# untitled2-6.net
KiCad netlist of a schematic drawn in EAGLE
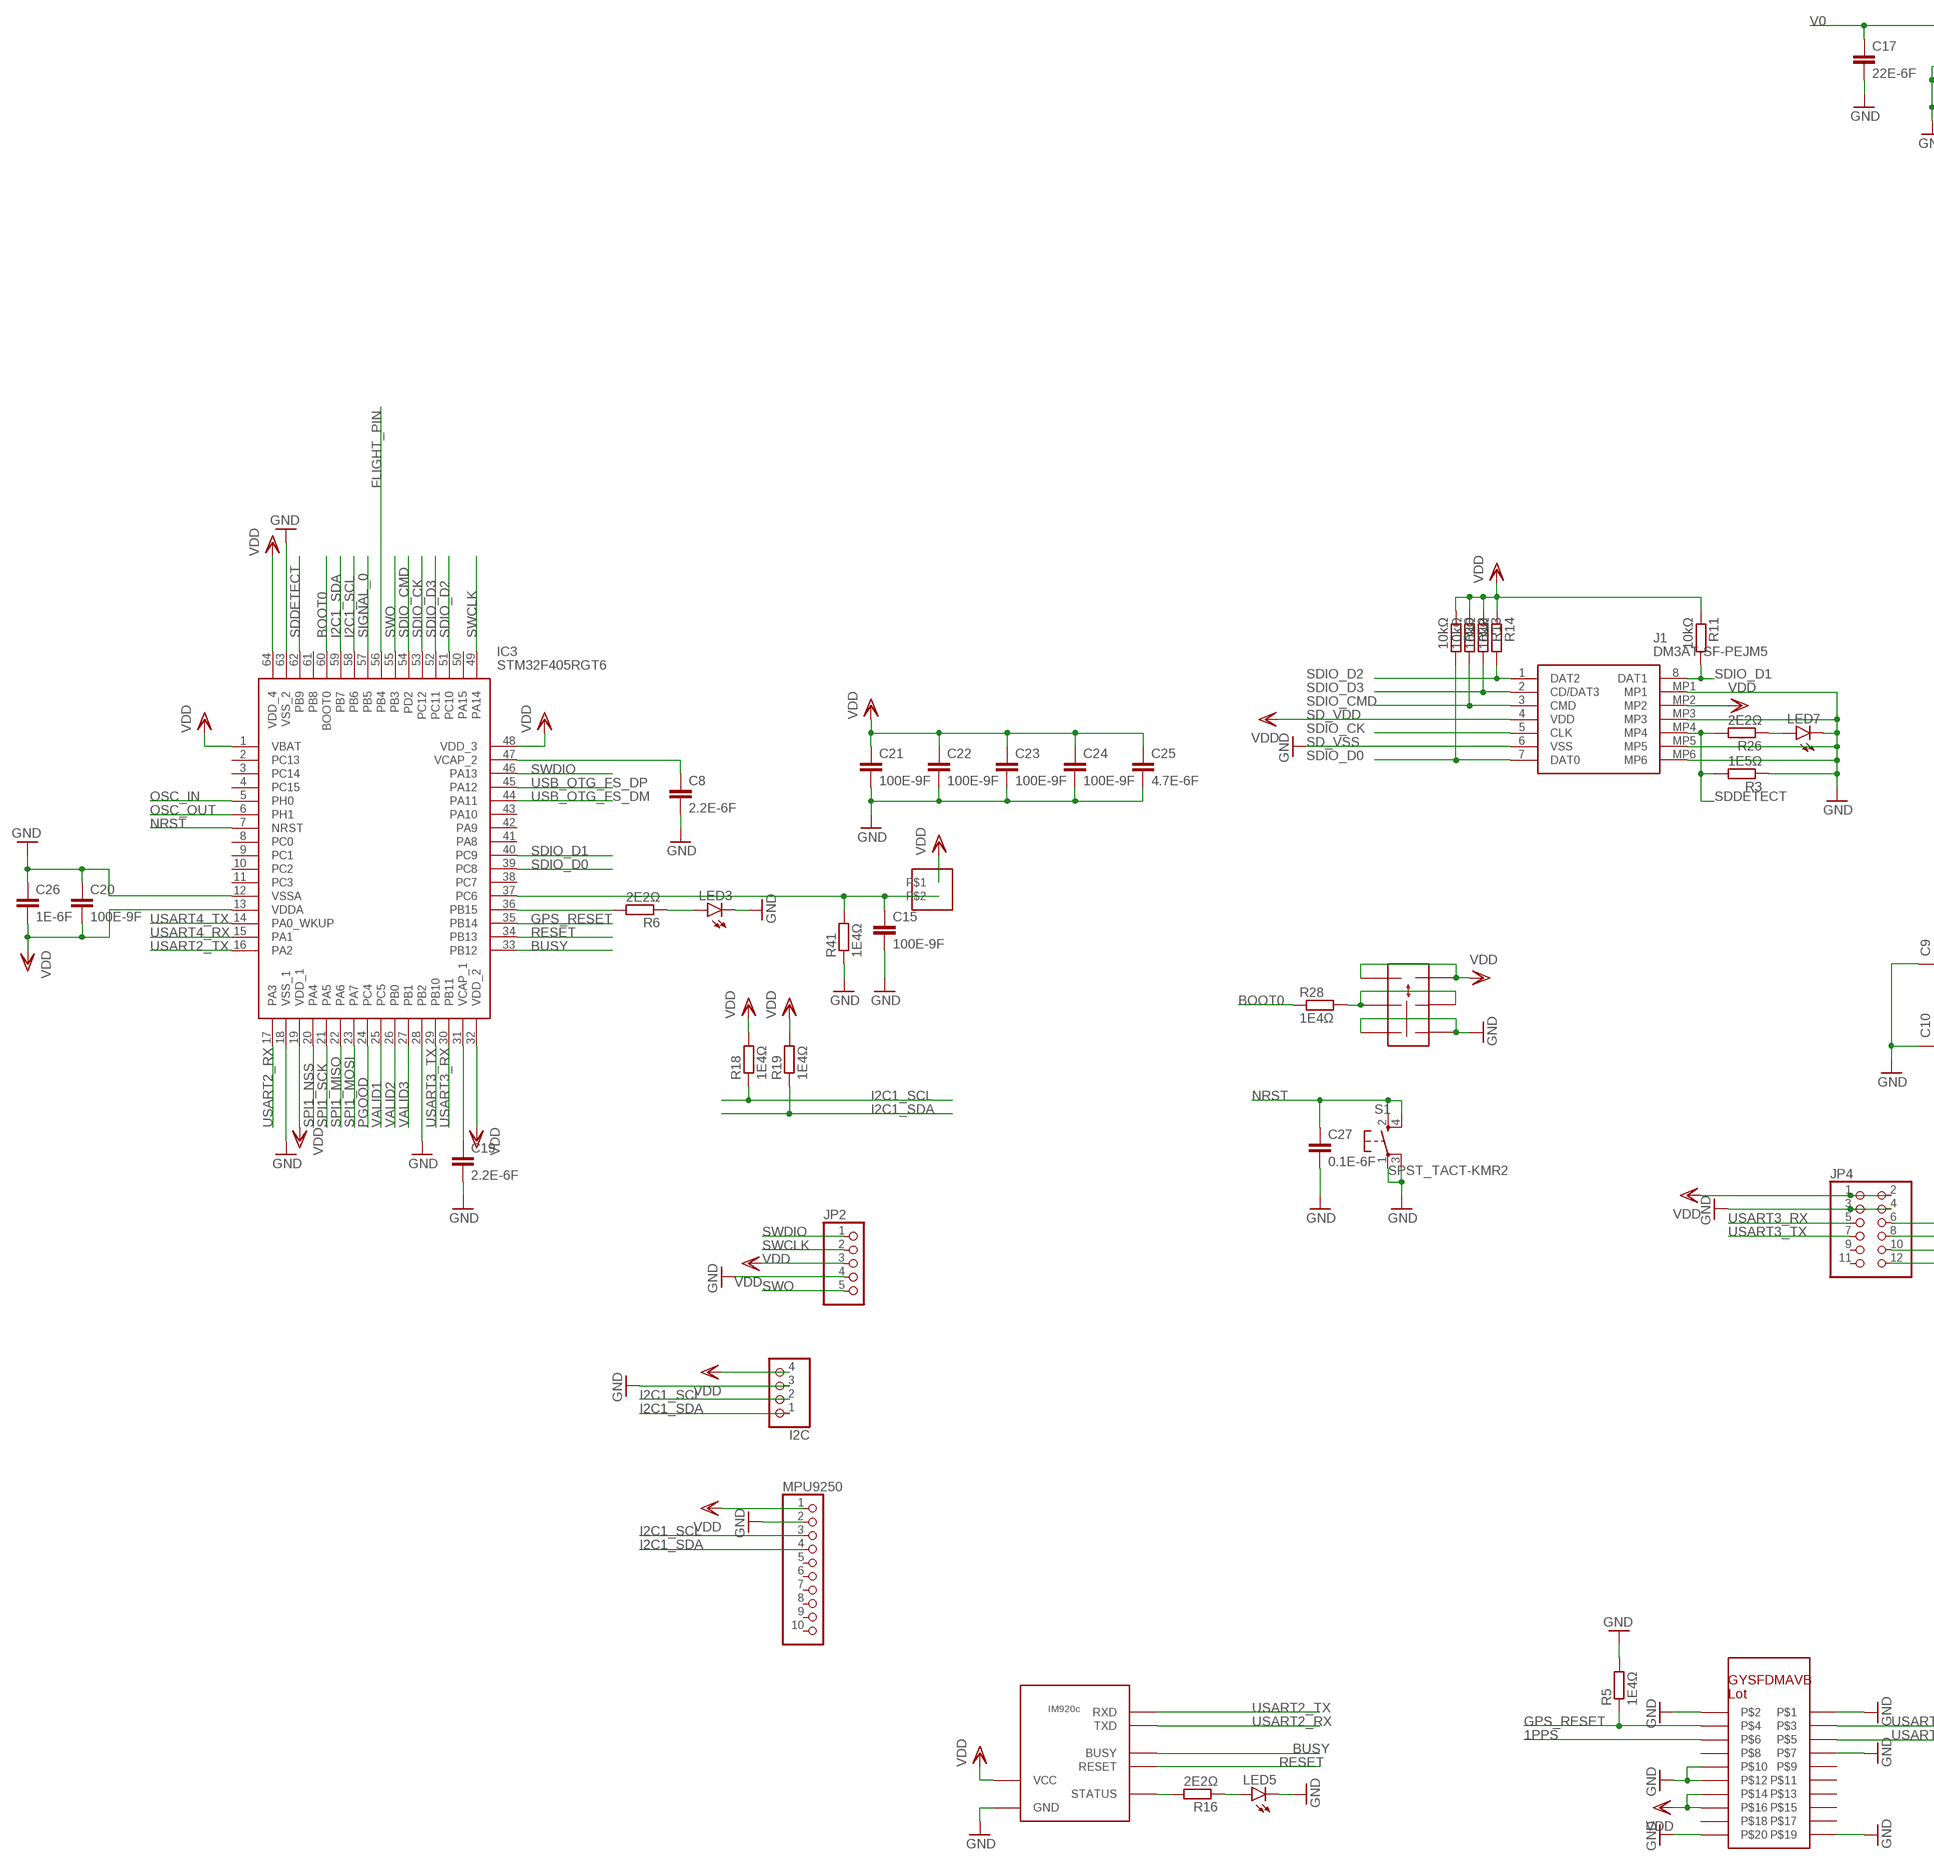
[diagram p0: schematic, sheet 1, part 1 of 2]
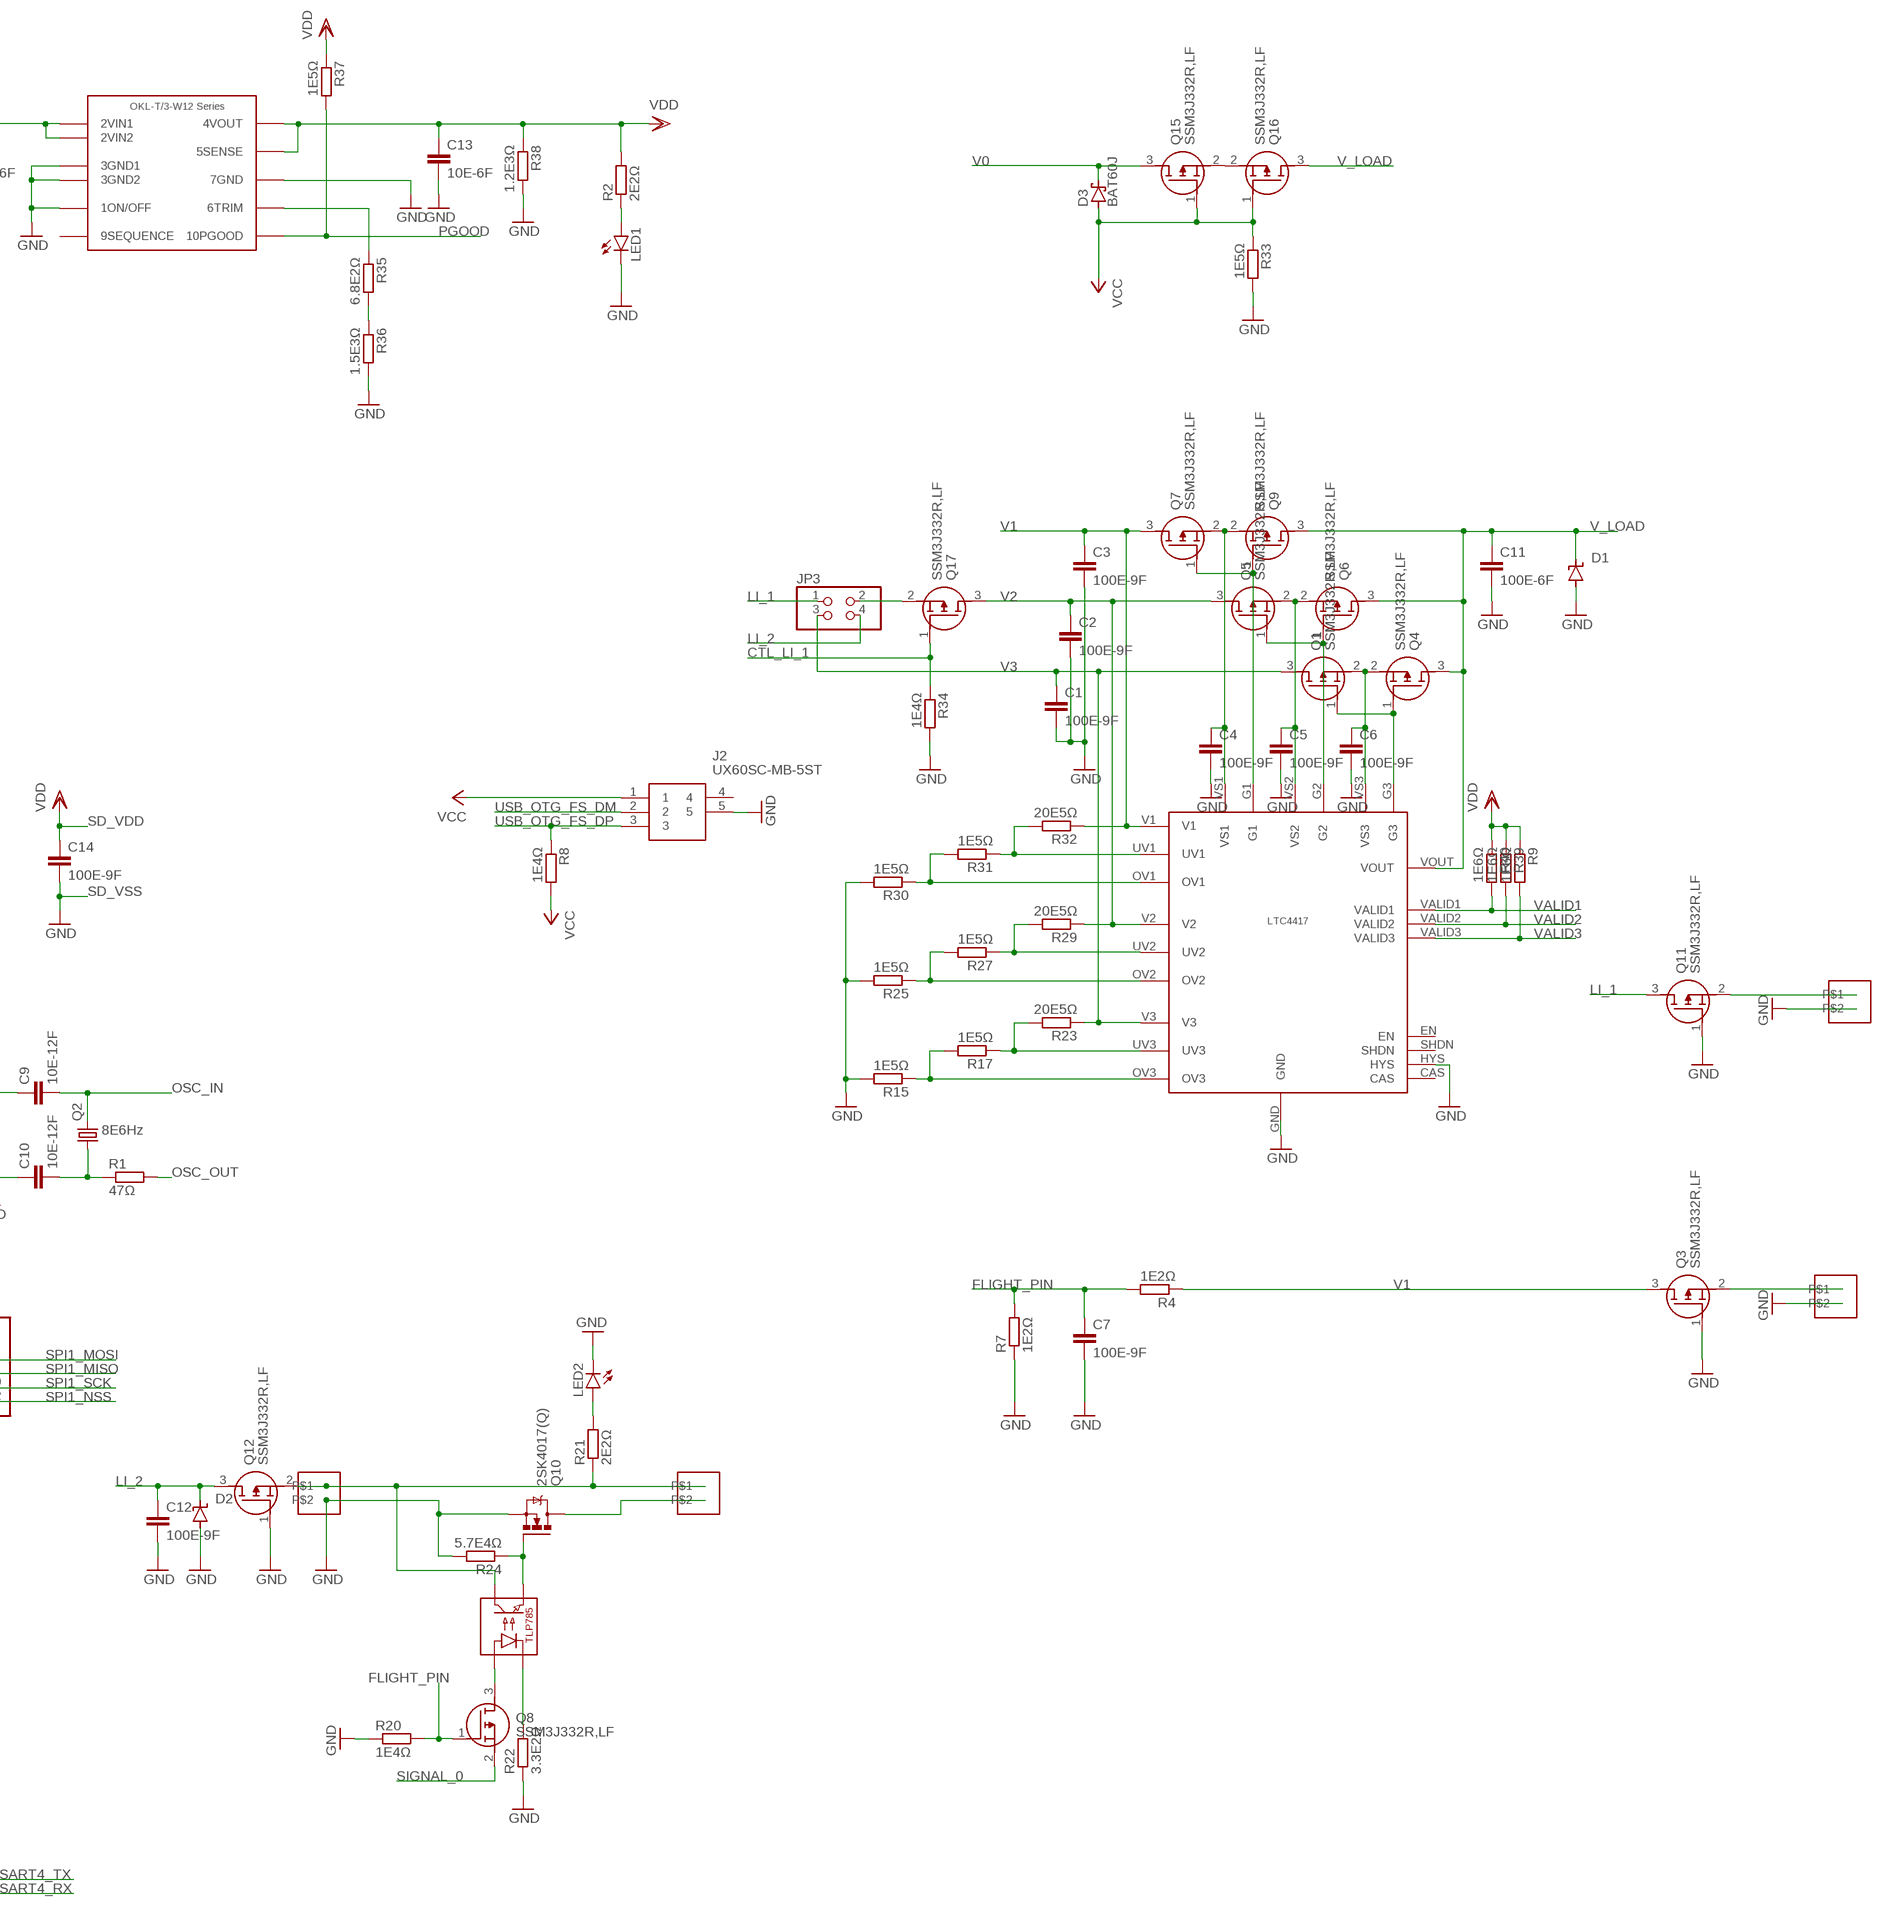
[diagram p1: schematic, sheet 1, part 2 of 2]

(export (version "E")
  (design (tool "Eeschema 10.0.6"))
  (components
    (comp (ref "C1")
      (value "100E-9F")
      (footprint "eagle-import:C0805")
      (libsource (lib "eagle-import") (part "C-EUC0805"))
    )
    (comp (ref "C2")
      (value "100E-9F")
      (footprint "eagle-import:C0805")
      (libsource (lib "eagle-import") (part "C-EUC0805"))
    )
    (comp (ref "C3")
      (value "100E-9F")
      (footprint "eagle-import:C0805")
      (libsource (lib "eagle-import") (part "C-EUC0805"))
    )
    (comp (ref "C4")
      (value "100E-9F")
      (footprint "eagle-import:C0805")
      (libsource (lib "eagle-import") (part "C-EUC0805"))
    )
    (comp (ref "C5")
      (value "100E-9F")
      (footprint "eagle-import:C0805")
      (libsource (lib "eagle-import") (part "C-EUC0805"))
    )
    (comp (ref "C6")
      (value "100E-9F")
      (footprint "eagle-import:C0805")
      (libsource (lib "eagle-import") (part "C-EUC0805"))
    )
    (comp (ref "C7")
      (value "100E-9F")
      (footprint "eagle-import:C0805")
      (libsource (lib "eagle-import") (part "C-EUC0805"))
    )
    (comp (ref "C8")
      (value "2.2E-6F")
      (footprint "eagle-import:C0805")
      (libsource (lib "eagle-import") (part "C-EUC0805"))
    )
    (comp (ref "C9")
      (value "10E-12F")
      (footprint "eagle-import:C0805")
      (libsource (lib "eagle-import") (part "C-EUC0805"))
    )
    (comp (ref "C10")
      (value "10E-12F")
      (footprint "eagle-import:C0805")
      (libsource (lib "eagle-import") (part "C-EUC0805"))
    )
    (comp (ref "C11")
      (value "100E-6F")
      (footprint "eagle-import:C0805")
      (libsource (lib "eagle-import") (part "C-EUC0805"))
    )
    (comp (ref "C12")
      (value "100E-9F")
      (footprint "eagle-import:C0805")
      (libsource (lib "eagle-import") (part "C-EUC0805"))
    )
    (comp (ref "C13")
      (value "10E-6F")
      (footprint "eagle-import:C0805")
      (libsource (lib "eagle-import") (part "C-EUC0805"))
    )
    (comp (ref "C14")
      (value "100E-9F")
      (footprint "eagle-import:C0805")
      (libsource (lib "eagle-import") (part "C-EUC0805"))
    )
    (comp (ref "C15")
      (value "100E-9F")
      (footprint "eagle-import:C0805")
      (libsource (lib "eagle-import") (part "C-EUC0805"))
    )
    (comp (ref "C17")
      (value "22E-6F")
      (footprint "eagle-import:C0805")
      (libsource (lib "eagle-import") (part "C-EUC0805"))
    )
    (comp (ref "C19")
      (value "2.2E-6F")
      (footprint "eagle-import:C0805")
      (libsource (lib "eagle-import") (part "C-EUC0805"))
    )
    (comp (ref "C20")
      (value "100E-9F")
      (footprint "eagle-import:C0805")
      (libsource (lib "eagle-import") (part "C-EUC0805"))
    )
    (comp (ref "C21")
      (value "100E-9F")
      (footprint "eagle-import:C0805")
      (libsource (lib "eagle-import") (part "C-EUC0805"))
    )
    (comp (ref "C22")
      (value "100E-9F")
      (footprint "eagle-import:C0805")
      (libsource (lib "eagle-import") (part "C-EUC0805"))
    )
    (comp (ref "C23")
      (value "100E-9F")
      (footprint "eagle-import:C0805")
      (libsource (lib "eagle-import") (part "C-EUC0805"))
    )
    (comp (ref "C24")
      (value "100E-9F")
      (footprint "eagle-import:C0805")
      (libsource (lib "eagle-import") (part "C-EUC0805"))
    )
    (comp (ref "C25")
      (value "4.7E-6F")
      (footprint "eagle-import:C0805")
      (libsource (lib "eagle-import") (part "C-EUC0805"))
    )
    (comp (ref "C26")
      (value "1E-6F")
      (footprint "eagle-import:C0805")
      (libsource (lib "eagle-import") (part "C-EUC0805"))
    )
    (comp (ref "C27")
      (value "0.1E-6F")
      (footprint "eagle-import:C0805")
      (libsource (lib "eagle-import") (part "C-EUC0805"))
    )
    (comp (ref "D1")
      (value "SUPPRESSOR-SMBJ")
      (footprint "eagle-import:SMBJ")
      (libsource (lib "eagle-import") (part "SUPPRESSOR-SMBJ"))
    )
    (comp (ref "D2")
      (value "SUPPRESSOR-SMBJ")
      (footprint "eagle-import:SMBJ")
      (libsource (lib "eagle-import") (part "SUPPRESSOR-SMBJ"))
    )
    (comp (ref "D3")
      (value "BAT60J")
      (footprint "eagle-import:SOD323_ST")
      (libsource (lib "eagle-import") (part "BAT60J"))
    )
    (comp (ref "I2C")
      (value "PINHD-1X4")
      (footprint "eagle-import:1X04")
      (libsource (lib "eagle-import") (part "PINHD-1X4"))
    )
    (comp (ref "IC3")
      (value "STM32F405RGT6")
      (footprint "eagle-import:QFP50P1200X1200X160-64N")
      (fields (field (name "MOUSER_PART_NUMBER") "511-STM32F405RGT6"))
      (libsource (lib "eagle-import") (part "STM32F405RGT6"))
    )
    (comp (ref "J1")
      (value "DM3AT-SF-PEJM5")
      (footprint "eagle-import:DM3ATSFPEJM5")
      (fields (field (name "MOUSER_PART_NUMBER") "798-DM3AT-SF-PEJM5"))
      (libsource (lib "eagle-import") (part "DM3AT-SF-PEJM5"))
    )
    (comp (ref "J2")
      (value "UX60SC-MB-5ST")
      (footprint "eagle-import:UX60SC-MB-5ST")
      (fields (field (name "MOUSER_PART_NUMBER") "798-UX60SC-MB-5ST"))
      (libsource (lib "eagle-import") (part "UX60SC-MB-5ST"))
    )
    (comp (ref "JP2")
      (value "PINHD-1X5")
      (footprint "eagle-import:1X05")
      (libsource (lib "eagle-import") (part "PINHD-1X5"))
    )
    (comp (ref "JP3")
      (value "PINHD-2X2")
      (footprint "eagle-import:2X02")
      (libsource (lib "eagle-import") (part "PINHD-2X2"))
    )
    (comp (ref "JP4")
      (value "PINHD-2X6")
      (footprint "eagle-import:2X06")
      (libsource (lib "eagle-import") (part "PINHD-2X6"))
    )
    (comp (ref "LED1")
      (value "LEDCHIP-LED0805")
      (footprint "eagle-import:CHIP-LED0805")
      (libsource (lib "eagle-import") (part "LEDCHIP-LED0805"))
    )
    (comp (ref "LED2")
      (value "LEDCHIP-LED0805")
      (footprint "eagle-import:CHIP-LED0805")
      (libsource (lib "eagle-import") (part "LEDCHIP-LED0805"))
    )
    (comp (ref "LED3")
      (value "LEDCHIP-LED0805")
      (footprint "eagle-import:CHIP-LED0805")
      (libsource (lib "eagle-import") (part "LEDCHIP-LED0805"))
    )
    (comp (ref "LED5")
      (value "LEDCHIP-LED0805")
      (footprint "eagle-import:CHIP-LED0805")
      (libsource (lib "eagle-import") (part "LEDCHIP-LED0805"))
    )
    (comp (ref "LED7")
      (value "LEDCHIP-LED0805")
      (footprint "eagle-import:CHIP-LED0805")
      (libsource (lib "eagle-import") (part "LEDCHIP-LED0805"))
    )
    (comp (ref "MPU9250")
      (value "PINHD-1X10")
      (footprint "eagle-import:1X10")
      (libsource (lib "eagle-import") (part "PINHD-1X10"))
    )
    (comp (ref "Q1")
      (value "SSM3J332R,LF")
      (footprint "eagle-import:2-3Z1S(SOT-23F)")
      (fields (field (name "MOUSER_PART_NUMBER") "757-SSM3J332RLF"))
      (libsource (lib "eagle-import") (part "SSM3J332R,LF"))
    )
    (comp (ref "Q2")
      (value "CRYSTALCTS406")
      (footprint "eagle-import:CTS406")
      (libsource (lib "eagle-import") (part "CRYSTALCTS406"))
    )
    (comp (ref "Q3")
      (value "SSM3J332R,LF")
      (footprint "eagle-import:2-3Z1S(SOT-23F)")
      (fields (field (name "MOUSER_PART_NUMBER") "757-SSM3J332RLF"))
      (libsource (lib "eagle-import") (part "SSM3J332R,LF"))
    )
    (comp (ref "Q4")
      (value "SSM3J332R,LF")
      (footprint "eagle-import:2-3Z1S(SOT-23F)")
      (fields (field (name "MOUSER_PART_NUMBER") "757-SSM3J332RLF"))
      (libsource (lib "eagle-import") (part "SSM3J332R,LF"))
    )
    (comp (ref "Q5")
      (value "SSM3J332R,LF")
      (footprint "eagle-import:2-3Z1S(SOT-23F)")
      (fields (field (name "MOUSER_PART_NUMBER") "757-SSM3J332RLF"))
      (libsource (lib "eagle-import") (part "SSM3J332R,LF"))
    )
    (comp (ref "Q6")
      (value "SSM3J332R,LF")
      (footprint "eagle-import:2-3Z1S(SOT-23F)")
      (fields (field (name "MOUSER_PART_NUMBER") "757-SSM3J332RLF"))
      (libsource (lib "eagle-import") (part "SSM3J332R,LF"))
    )
    (comp (ref "Q7")
      (value "SSM3J332R,LF")
      (footprint "eagle-import:2-3Z1S(SOT-23F)")
      (fields (field (name "MOUSER_PART_NUMBER") "757-SSM3J332RLF"))
      (libsource (lib "eagle-import") (part "SSM3J332R,LF"))
    )
    (comp (ref "Q8")
      (value "SSM3J332R,LF")
      (footprint "eagle-import:2-3Z1S(SOT-23F)")
      (fields (field (name "MOUSER_PART_NUMBER") "757-SSM3J332RLF"))
      (libsource (lib "eagle-import") (part "SSM3J332R,LF"))
    )
    (comp (ref "Q9")
      (value "SSM3J332R,LF")
      (footprint "eagle-import:2-3Z1S(SOT-23F)")
      (fields (field (name "MOUSER_PART_NUMBER") "757-SSM3J332RLF"))
      (libsource (lib "eagle-import") (part "SSM3J332R,LF"))
    )
    (comp (ref "Q10")
      (value "2SK4017(Q)")
      (footprint "eagle-import:TO230P230X650X740-3P")
      (fields (field (name "MF") "Toshiba Semiconductor"))
      (libsource (lib "eagle-import") (part "2SK4017(Q)"))
    )
    (comp (ref "Q11")
      (value "SSM3J332R,LF")
      (footprint "eagle-import:2-3Z1S(SOT-23F)")
      (fields (field (name "MOUSER_PART_NUMBER") "757-SSM3J332RLF"))
      (libsource (lib "eagle-import") (part "SSM3J332R,LF"))
    )
    (comp (ref "Q12")
      (value "SSM3J332R,LF")
      (footprint "eagle-import:2-3Z1S(SOT-23F)")
      (fields (field (name "MOUSER_PART_NUMBER") "757-SSM3J332RLF"))
      (libsource (lib "eagle-import") (part "SSM3J332R,LF"))
    )
    (comp (ref "Q15")
      (value "SSM3J332R,LF")
      (footprint "eagle-import:2-3Z1S(SOT-23F)")
      (fields (field (name "MOUSER_PART_NUMBER") "757-SSM3J332RLF"))
      (libsource (lib "eagle-import") (part "SSM3J332R,LF"))
    )
    (comp (ref "Q16")
      (value "SSM3J332R,LF")
      (footprint "eagle-import:2-3Z1S(SOT-23F)")
      (fields (field (name "MOUSER_PART_NUMBER") "757-SSM3J332RLF"))
      (libsource (lib "eagle-import") (part "SSM3J332R,LF"))
    )
    (comp (ref "Q17")
      (value "SSM3J332R,LF")
      (footprint "eagle-import:2-3Z1S(SOT-23F)")
      (fields (field (name "MOUSER_PART_NUMBER") "757-SSM3J332RLF"))
      (libsource (lib "eagle-import") (part "SSM3J332R,LF"))
    )
    (comp (ref "R1")
      (value "47Ω")
      (footprint "eagle-import:R0603")
      (libsource (lib "eagle-import") (part "R-EU_R0603"))
    )
    (comp (ref "R2")
      (value "2E2Ω")
      (footprint "eagle-import:R0603")
      (libsource (lib "eagle-import") (part "R-EU_R0603"))
    )
    (comp (ref "R3")
      (value "1E5Ω")
      (footprint "eagle-import:R0603")
      (libsource (lib "eagle-import") (part "R-EU_R0603"))
    )
    (comp (ref "R4")
      (value "1E2Ω")
      (footprint "eagle-import:R0603")
      (libsource (lib "eagle-import") (part "R-EU_R0603"))
    )
    (comp (ref "R5")
      (value "1E4Ω")
      (footprint "eagle-import:R0603")
      (libsource (lib "eagle-import") (part "R-EU_R0603"))
    )
    (comp (ref "R6")
      (value "2E2Ω")
      (footprint "eagle-import:R0603")
      (libsource (lib "eagle-import") (part "R-EU_R0603"))
    )
    (comp (ref "R7")
      (value "1E2Ω")
      (footprint "eagle-import:R0603")
      (libsource (lib "eagle-import") (part "R-EU_R0603"))
    )
    (comp (ref "R8")
      (value "1E4Ω")
      (footprint "eagle-import:R0603")
      (libsource (lib "eagle-import") (part "R-EU_R0603"))
    )
    (comp (ref "R9")
      (value "1E6Ω")
      (footprint "eagle-import:R0603")
      (libsource (lib "eagle-import") (part "R-EU_R0603"))
    )
    (comp (ref "R10")
      (value "10kΩ")
      (footprint "eagle-import:R0603")
      (libsource (lib "eagle-import") (part "R-EU_R0603"))
    )
    (comp (ref "R11")
      (value "10kΩ")
      (footprint "eagle-import:R0603")
      (libsource (lib "eagle-import") (part "R-EU_R0603"))
    )
    (comp (ref "R12")
      (value "10kΩ")
      (footprint "eagle-import:R0603")
      (libsource (lib "eagle-import") (part "R-EU_R0603"))
    )
    (comp (ref "R13")
      (value "10kΩ")
      (footprint "eagle-import:R0603")
      (libsource (lib "eagle-import") (part "R-EU_R0603"))
    )
    (comp (ref "R14")
      (value "10kΩ")
      (footprint "eagle-import:R0603")
      (libsource (lib "eagle-import") (part "R-EU_R0603"))
    )
    (comp (ref "R15")
      (value "1E5Ω")
      (footprint "eagle-import:R0603")
      (libsource (lib "eagle-import") (part "R-EU_R0603"))
    )
    (comp (ref "R16")
      (value "2E2Ω")
      (footprint "eagle-import:R0603")
      (libsource (lib "eagle-import") (part "R-EU_R0603"))
    )
    (comp (ref "R17")
      (value "1E5Ω")
      (footprint "eagle-import:R0603")
      (libsource (lib "eagle-import") (part "R-EU_R0603"))
    )
    (comp (ref "R18")
      (value "1E4Ω")
      (footprint "eagle-import:R0603")
      (libsource (lib "eagle-import") (part "R-EU_R0603"))
    )
    (comp (ref "R19")
      (value "1E4Ω")
      (footprint "eagle-import:R0603")
      (libsource (lib "eagle-import") (part "R-EU_R0603"))
    )
    (comp (ref "R20")
      (value "1E4Ω")
      (footprint "eagle-import:R0603")
      (libsource (lib "eagle-import") (part "R-EU_R0603"))
    )
    (comp (ref "R21")
      (value "2E2Ω")
      (footprint "eagle-import:R0603")
      (libsource (lib "eagle-import") (part "R-EU_R0603"))
    )
    (comp (ref "R22")
      (value "3.3E2Ω")
      (footprint "eagle-import:R0603")
      (libsource (lib "eagle-import") (part "R-EU_R0603"))
    )
    (comp (ref "R23")
      (value "20E5Ω")
      (footprint "eagle-import:R0603")
      (libsource (lib "eagle-import") (part "R-EU_R0603"))
    )
    (comp (ref "R24")
      (value "5.7E4Ω")
      (footprint "eagle-import:R0603")
      (libsource (lib "eagle-import") (part "R-EU_R0603"))
    )
    (comp (ref "R25")
      (value "1E5Ω")
      (footprint "eagle-import:R0603")
      (libsource (lib "eagle-import") (part "R-EU_R0603"))
    )
    (comp (ref "R26")
      (value "2E2Ω")
      (footprint "eagle-import:R0603")
      (libsource (lib "eagle-import") (part "R-EU_R0603"))
    )
    (comp (ref "R27")
      (value "1E5Ω")
      (footprint "eagle-import:R0603")
      (libsource (lib "eagle-import") (part "R-EU_R0603"))
    )
    (comp (ref "R28")
      (value "1E4Ω")
      (footprint "eagle-import:R0603")
      (libsource (lib "eagle-import") (part "R-EU_R0603"))
    )
    (comp (ref "R29")
      (value "20E5Ω")
      (footprint "eagle-import:R0603")
      (libsource (lib "eagle-import") (part "R-EU_R0603"))
    )
    (comp (ref "R30")
      (value "1E5Ω")
      (footprint "eagle-import:R0603")
      (libsource (lib "eagle-import") (part "R-EU_R0603"))
    )
    (comp (ref "R31")
      (value "1E5Ω")
      (footprint "eagle-import:R0603")
      (libsource (lib "eagle-import") (part "R-EU_R0603"))
    )
    (comp (ref "R32")
      (value "20E5Ω")
      (footprint "eagle-import:R0603")
      (libsource (lib "eagle-import") (part "R-EU_R0603"))
    )
    (comp (ref "R33")
      (value "1E5Ω")
      (footprint "eagle-import:R0603")
      (libsource (lib "eagle-import") (part "R-EU_R0603"))
    )
    (comp (ref "R34")
      (value "1E4Ω")
      (footprint "eagle-import:R0603")
      (libsource (lib "eagle-import") (part "R-EU_R0603"))
    )
    (comp (ref "R35")
      (value "6.8E2Ω")
      (footprint "eagle-import:R0603")
      (libsource (lib "eagle-import") (part "R-EU_R0603"))
    )
    (comp (ref "R36")
      (value "1.5E3Ω")
      (footprint "eagle-import:R0603")
      (libsource (lib "eagle-import") (part "R-EU_R0603"))
    )
    (comp (ref "R37")
      (value "1E5Ω")
      (footprint "eagle-import:R0603")
      (libsource (lib "eagle-import") (part "R-EU_R0603"))
    )
    (comp (ref "R38")
      (value "1.2E3Ω")
      (footprint "eagle-import:R0603")
      (libsource (lib "eagle-import") (part "R-EU_R0603"))
    )
    (comp (ref "R39")
      (value "1E6Ω")
      (footprint "eagle-import:R0603")
      (libsource (lib "eagle-import") (part "R-EU_R0603"))
    )
    (comp (ref "R40")
      (value "1E6Ω")
      (footprint "eagle-import:R0603")
      (libsource (lib "eagle-import") (part "R-EU_R0603"))
    )
    (comp (ref "R41")
      (value "1E4Ω")
      (footprint "eagle-import:R0603")
      (libsource (lib "eagle-import") (part "R-EU_R0603"))
    )
    (comp (ref "S1")
      (value "SPST_TACT-KMR2")
      (footprint "eagle-import:KMR2")
      (libsource (lib "eagle-import") (part "SPST_TACT-KMR2"))
    )
    (comp (ref "TRANSISTER2")
      (value "TLP785")
      (footprint "eagle-import:TLP785")
      (libsource (lib "eagle-import") (part "TLP785"))
    )
    (comp (ref "U$1")
      (value "B2B-XH-A")
      (footprint "eagle-import:B2B-XH-A")
      (libsource (lib "eagle-import") (part "B2B-XH-A"))
    )
    (comp (ref "U$2")
      (value "LTC4417")
      (footprint "eagle-import:LTC4417")
      (libsource (lib "eagle-import") (part "LTC4417"))
    )
    (comp (ref "U$3")
      (value "OKL-T/3-W12SERIES")
      (footprint "eagle-import:OKL-T_3-W12SERIES")
      (libsource (lib "eagle-import") (part "OKL-T/3-W12SERIES"))
    )
    (comp (ref "U$4")
      (value "GYSFDMAXB_LOT")
      (footprint "eagle-import:GYSFDMAXB_LOT")
      (libsource (lib "eagle-import") (part "GYSFDMAXB_LOT"))
    )
    (comp (ref "U$5")
      (value "IM920C")
      (footprint "eagle-import:IM920C")
      (libsource (lib "eagle-import") (part "IM920C"))
    )
    (comp (ref "U$6")
      (value "B2B-XH-A")
      (footprint "eagle-import:B2B-XH-A")
      (libsource (lib "eagle-import") (part "B2B-XH-A"))
    )
    (comp (ref "U$7")
      (value "B2B-XH-A")
      (footprint "eagle-import:B2B-XH-A")
      (libsource (lib "eagle-import") (part "B2B-XH-A"))
    )
    (comp (ref "U$8")
      (value "B2B-XH-A")
      (footprint "eagle-import:B2B-XH-A")
      (libsource (lib "eagle-import") (part "B2B-XH-A"))
    )
    (comp (ref "U$9")
      (value "SSSS213202")
      (footprint "eagle-import:SSSS213202")
      (libsource (lib "eagle-import") (part "SSSS213202"))
    )
    (comp (ref "U$10")
      (value "B2B-XH-A")
      (footprint "eagle-import:B2B-XH-A")
      (libsource (lib "eagle-import") (part "B2B-XH-A"))
    )
  )
  (nets
    (net (code "1") (name "/1PPS") (class "Default")
      (node (ref "U$4") (pin "P$6") (pinfunction "P$6_P$6") (pintype "bidirectional"))
    )
    (net (code "2") (name "/BOOT0") (class "Default")
      (node (ref "IC3") (pin "60") (pinfunction "BOOT0_60") (pintype "bidirectional"))
      (node (ref "R28") (pin "1") (pinfunction "1_1") (pintype "passive"))
    )
    (net (code "3") (name "/BUSY") (class "Default")
      (node (ref "IC3") (pin "33") (pinfunction "PB12_33") (pintype "bidirectional"))
      (node (ref "U$5") (pin "BUSY") (pinfunction "BUSY_BUSY") (pintype "bidirectional"))
    )
    (net (code "4") (name "/CTL_LI_1") (class "Default")
      (node (ref "Q17") (pin "1") (pinfunction "G_1") (pintype "bidirectional"))
      (node (ref "R34") (pin "1") (pinfunction "1_1") (pintype "passive"))
    )
    (net (code "5") (name "/FLIGHT_PIN") (class "Default")
      (node (ref "C7") (pin "1") (pinfunction "1_1") (pintype "passive"))
      (node (ref "IC3") (pin "56") (pinfunction "PB4_56") (pintype "bidirectional"))
      (node (ref "Q8") (pin "1") (pinfunction "G_1") (pintype "bidirectional"))
      (node (ref "R20") (pin "2") (pinfunction "2_2") (pintype "passive"))
      (node (ref "R4") (pin "2") (pinfunction "2_2") (pintype "passive"))
      (node (ref "R7") (pin "2") (pinfunction "2_2") (pintype "passive"))
    )
    (net (code "6") (name "/GPS_RESET") (class "Default")
      (node (ref "IC3") (pin "35") (pinfunction "PB14_35") (pintype "bidirectional"))
      (node (ref "R5") (pin "1") (pinfunction "1_1") (pintype "passive"))
      (node (ref "U$4") (pin "P$4") (pinfunction "P$4_P$4") (pintype "bidirectional"))
    )
    (net (code "7") (name "/I2C1_SCL") (class "Default")
      (node (ref "I2C") (pin "2") (pinfunction "2_2") (pintype "passive"))
      (node (ref "IC3") (pin "58") (pinfunction "PB6_58") (pintype "bidirectional"))
      (node (ref "MPU9250") (pin "3") (pinfunction "3_3") (pintype "passive"))
      (node (ref "R18") (pin "1") (pinfunction "1_1") (pintype "passive"))
    )
    (net (code "8") (name "/I2C1_SDA") (class "Default")
      (node (ref "I2C") (pin "1") (pinfunction "1_1") (pintype "passive"))
      (node (ref "IC3") (pin "59") (pinfunction "PB7_59") (pintype "bidirectional"))
      (node (ref "MPU9250") (pin "4") (pinfunction "4_4") (pintype "passive"))
      (node (ref "R19") (pin "1") (pinfunction "1_1") (pintype "passive"))
    )
    (net (code "9") (name "/LI_1") (class "Default")
      (node (ref "JP3") (pin "1") (pinfunction "1_1") (pintype "passive"))
      (node (ref "Q11") (pin "3") (pinfunction "D_3") (pintype "bidirectional"))
    )
    (net (code "10") (name "/LI_2") (class "Default")
      (node (ref "C12") (pin "1") (pinfunction "1_1") (pintype "passive"))
      (node (ref "D2") (pin "C") (pinfunction "C_C") (pintype "passive"))
      (node (ref "JP3") (pin "4") (pinfunction "4_4") (pintype "passive"))
      (node (ref "Q12") (pin "3") (pinfunction "D_3") (pintype "bidirectional"))
    )
    (net (code "11") (name "/NRST") (class "Default")
      (node (ref "C27") (pin "1") (pinfunction "1_1") (pintype "passive"))
      (node (ref "IC3") (pin "7") (pinfunction "NRST_7") (pintype "bidirectional"))
      (node (ref "S1") (pin "2") (pinfunction "S_2") (pintype "passive"))
      (node (ref "S1") (pin "4") (pinfunction "S1_4") (pintype "passive"))
    )
    (net (code "12") (name "/OSC_IN") (class "Default")
      (node (ref "C9") (pin "2") (pinfunction "2_2") (pintype "passive"))
      (node (ref "IC3") (pin "5") (pinfunction "PH0_5") (pintype "bidirectional"))
      (node (ref "Q2") (pin "3") (pinfunction "2_3") (pintype "passive"))
    )
    (net (code "13") (name "/OSC_OUT") (class "Default")
      (node (ref "IC3") (pin "6") (pinfunction "PH1_6") (pintype "bidirectional"))
      (node (ref "R1") (pin "2") (pinfunction "2_2") (pintype "passive"))
    )
    (net (code "14") (name "/PGOOD") (class "Default")
      (node (ref "IC3") (pin "24") (pinfunction "PC4_24") (pintype "bidirectional"))
      (node (ref "R37") (pin "2") (pinfunction "2_2") (pintype "passive"))
      (node (ref "U$3") (pin "10PGOOD") (pinfunction "10PGOOD_10PGOOD") (pintype "bidirectional"))
    )
    (net (code "15") (name "/RESET") (class "Default")
      (node (ref "IC3") (pin "34") (pinfunction "PB13_34") (pintype "bidirectional"))
      (node (ref "U$5") (pin "RESET") (pinfunction "RESET_RESET") (pintype "bidirectional"))
    )
    (net (code "16") (name "/SDDETECT") (class "Default")
      (node (ref "IC3") (pin "62") (pinfunction "PB9_62") (pintype "bidirectional"))
      (node (ref "J1") (pin "MP4") (pinfunction "MP4_MP4") (pintype "bidirectional"))
      (node (ref "R26") (pin "2") (pinfunction "2_2") (pintype "passive"))
      (node (ref "R3") (pin "2") (pinfunction "2_2") (pintype "passive"))
    )
    (net (code "17") (name "/SDIO_CK") (class "Default")
      (node (ref "IC3") (pin "53") (pinfunction "PC12_53") (pintype "bidirectional"))
      (node (ref "J1") (pin "5") (pinfunction "CLK_5") (pintype "bidirectional"))
    )
    (net (code "18") (name "/SDIO_CMD") (class "Default")
      (node (ref "IC3") (pin "54") (pinfunction "PD2_54") (pintype "bidirectional"))
      (node (ref "J1") (pin "3") (pinfunction "CMD_3") (pintype "bidirectional"))
      (node (ref "R12") (pin "2") (pinfunction "2_2") (pintype "passive"))
    )
    (net (code "19") (name "/SDIO_D0") (class "Default")
      (node (ref "IC3") (pin "39") (pinfunction "PC8_39") (pintype "bidirectional"))
      (node (ref "J1") (pin "7") (pinfunction "DAT0_7") (pintype "bidirectional"))
      (node (ref "R10") (pin "2") (pinfunction "2_2") (pintype "passive"))
    )
    (net (code "20") (name "/SDIO_D1") (class "Default")
      (node (ref "IC3") (pin "40") (pinfunction "PC9_40") (pintype "bidirectional"))
      (node (ref "J1") (pin "8") (pinfunction "DAT1_8") (pintype "bidirectional"))
      (node (ref "R11") (pin "2") (pinfunction "2_2") (pintype "passive"))
    )
    (net (code "21") (name "/SDIO_D2") (class "Default")
      (node (ref "IC3") (pin "51") (pinfunction "PC10_51") (pintype "bidirectional"))
      (node (ref "J1") (pin "1") (pinfunction "DAT2_1") (pintype "bidirectional"))
      (node (ref "R14") (pin "2") (pinfunction "2_2") (pintype "passive"))
    )
    (net (code "22") (name "/SDIO_D3") (class "Default")
      (node (ref "IC3") (pin "52") (pinfunction "PC11_52") (pintype "bidirectional"))
      (node (ref "J1") (pin "2") (pinfunction "CD/DAT3_2") (pintype "bidirectional"))
      (node (ref "R13") (pin "2") (pinfunction "2_2") (pintype "passive"))
    )
    (net (code "23") (name "/SIGNAL_0") (class "Default")
      (node (ref "IC3") (pin "57") (pinfunction "PB5_57") (pintype "bidirectional"))
      (node (ref "Q8") (pin "2") (pinfunction "S_2") (pintype "bidirectional"))
    )
    (net (code "24") (name "/SPI1_MISO") (class "Default")
      (node (ref "IC3") (pin "22") (pinfunction "PA6_22") (pintype "bidirectional"))
      (node (ref "JP4") (pin "8") (pinfunction "8_8") (pintype "passive"))
    )
    (net (code "25") (name "/SPI1_MOSI") (class "Default")
      (node (ref "IC3") (pin "23") (pinfunction "PA7_23") (pintype "bidirectional"))
      (node (ref "JP4") (pin "6") (pinfunction "6_6") (pintype "passive"))
    )
    (net (code "26") (name "/SPI1_NSS") (class "Default")
      (node (ref "IC3") (pin "20") (pinfunction "PA4_20") (pintype "bidirectional"))
      (node (ref "JP4") (pin "12") (pinfunction "12_12") (pintype "passive"))
    )
    (net (code "27") (name "/SPI1_SCK") (class "Default")
      (node (ref "IC3") (pin "21") (pinfunction "PA5_21") (pintype "bidirectional"))
      (node (ref "JP4") (pin "10") (pinfunction "10_10") (pintype "passive"))
    )
    (net (code "28") (name "/SWCLK") (class "Default")
      (node (ref "IC3") (pin "49") (pinfunction "PA14_49") (pintype "bidirectional"))
      (node (ref "JP2") (pin "2") (pinfunction "2_2") (pintype "passive"))
    )
    (net (code "29") (name "/SWDIO") (class "Default")
      (node (ref "IC3") (pin "46") (pinfunction "PA13_46") (pintype "bidirectional"))
      (node (ref "JP2") (pin "1") (pinfunction "1_1") (pintype "passive"))
    )
    (net (code "30") (name "/SWO") (class "Default")
      (node (ref "IC3") (pin "55") (pinfunction "PB3_55") (pintype "bidirectional"))
      (node (ref "JP2") (pin "5") (pinfunction "5_5") (pintype "passive"))
    )
    (net (code "31") (name "/USART2_RX") (class "Default")
      (node (ref "IC3") (pin "17") (pinfunction "PA3_17") (pintype "bidirectional"))
      (node (ref "U$5") (pin "TXD") (pinfunction "TXD_TXD") (pintype "bidirectional"))
    )
    (net (code "32") (name "/USART2_TX") (class "Default")
      (node (ref "IC3") (pin "16") (pinfunction "PA2_16") (pintype "bidirectional"))
      (node (ref "U$5") (pin "RXD") (pinfunction "RXD_RXD") (pintype "bidirectional"))
    )
    (net (code "33") (name "/USART3_RX") (class "Default")
      (node (ref "IC3") (pin "30") (pinfunction "PB11_30") (pintype "bidirectional"))
      (node (ref "JP4") (pin "5") (pinfunction "5_5") (pintype "passive"))
    )
    (net (code "34") (name "/USART3_TX") (class "Default")
      (node (ref "IC3") (pin "29") (pinfunction "PB10_29") (pintype "bidirectional"))
      (node (ref "JP4") (pin "7") (pinfunction "7_7") (pintype "passive"))
    )
    (net (code "35") (name "/USART4_RX") (class "Default")
      (node (ref "IC3") (pin "15") (pinfunction "PA1_15") (pintype "bidirectional"))
      (node (ref "U$4") (pin "P$5") (pinfunction "P$5_P$5") (pintype "bidirectional"))
    )
    (net (code "36") (name "/USART4_TX") (class "Default")
      (node (ref "IC3") (pin "14") (pinfunction "PA0_WKUP_14") (pintype "bidirectional"))
      (node (ref "U$4") (pin "P$3") (pinfunction "P$3_P$3") (pintype "bidirectional"))
    )
    (net (code "37") (name "/USB_OTG_FS_DM") (class "Default")
      (node (ref "IC3") (pin "44") (pinfunction "PA11_44") (pintype "bidirectional"))
      (node (ref "J2") (pin "2") (pinfunction "2_2") (pintype "bidirectional"))
    )
    (net (code "38") (name "/USB_OTG_FS_DP") (class "Default")
      (node (ref "IC3") (pin "45") (pinfunction "PA12_45") (pintype "bidirectional"))
      (node (ref "J2") (pin "3") (pinfunction "3_3") (pintype "bidirectional"))
      (node (ref "R8") (pin "1") (pinfunction "1_1") (pintype "passive"))
    )
    (net (code "39") (name "/V0") (class "Default")
      (node (ref "C17") (pin "1") (pinfunction "1_1") (pintype "passive"))
      (node (ref "D3") (pin "C") (pinfunction "C_C") (pintype "passive"))
      (node (ref "Q15") (pin "3") (pinfunction "D_3") (pintype "bidirectional"))
      (node (ref "U$3") (pin "2VIN1") (pinfunction "2VIN1_2VIN1") (pintype "bidirectional"))
      (node (ref "U$3") (pin "2VIN2") (pinfunction "2VIN2_2VIN2") (pintype "bidirectional"))
    )
    (net (code "40") (name "/V1") (class "Default")
      (node (ref "C3") (pin "1") (pinfunction "1_1") (pintype "passive"))
      (node (ref "Q3") (pin "3") (pinfunction "D_3") (pintype "bidirectional"))
      (node (ref "Q7") (pin "3") (pinfunction "D_3") (pintype "bidirectional"))
      (node (ref "R32") (pin "1") (pinfunction "1_1") (pintype "passive"))
      (node (ref "R4") (pin "1") (pinfunction "1_1") (pintype "passive"))
      (node (ref "U$2") (pin "V1") (pinfunction "V1_V1") (pintype "bidirectional"))
    )
    (net (code "41") (name "/V2") (class "Default")
      (node (ref "C2") (pin "1") (pinfunction "1_1") (pintype "passive"))
      (node (ref "Q17") (pin "3") (pinfunction "D_3") (pintype "bidirectional"))
      (node (ref "Q5") (pin "3") (pinfunction "D_3") (pintype "bidirectional"))
      (node (ref "R29") (pin "1") (pinfunction "1_1") (pintype "passive"))
      (node (ref "U$2") (pin "V2") (pinfunction "V2_V2") (pintype "bidirectional"))
    )
    (net (code "42") (name "/V3") (class "Default")
      (node (ref "C1") (pin "1") (pinfunction "1_1") (pintype "passive"))
      (node (ref "JP3") (pin "3") (pinfunction "3_3") (pintype "passive"))
      (node (ref "Q1") (pin "3") (pinfunction "D_3") (pintype "bidirectional"))
      (node (ref "R23") (pin "1") (pinfunction "1_1") (pintype "passive"))
      (node (ref "U$2") (pin "V3") (pinfunction "V3_V3") (pintype "bidirectional"))
    )
    (net (code "43") (name "/VALID1") (class "Default")
      (node (ref "IC3") (pin "25") (pinfunction "PC5_25") (pintype "bidirectional"))
      (node (ref "R40") (pin "2") (pinfunction "2_2") (pintype "passive"))
      (node (ref "U$2") (pin "VALID1") (pinfunction "VALID1_VALID1") (pintype "bidirectional"))
    )
    (net (code "44") (name "/VALID2") (class "Default")
      (node (ref "IC3") (pin "26") (pinfunction "PB0_26") (pintype "bidirectional"))
      (node (ref "R39") (pin "2") (pinfunction "2_2") (pintype "passive"))
      (node (ref "U$2") (pin "VALID2") (pinfunction "VALID2_VALID2") (pintype "bidirectional"))
    )
    (net (code "45") (name "/VALID3") (class "Default")
      (node (ref "IC3") (pin "27") (pinfunction "PB1_27") (pintype "bidirectional"))
      (node (ref "R9") (pin "2") (pinfunction "2_2") (pintype "passive"))
      (node (ref "U$2") (pin "VALID3") (pinfunction "VALID3_VALID3") (pintype "bidirectional"))
    )
    (net (code "46") (name "/V_LOAD") (class "Default")
      (node (ref "C11") (pin "1") (pinfunction "1_1") (pintype "passive"))
      (node (ref "D1") (pin "C") (pinfunction "C_C") (pintype "passive"))
      (node (ref "Q16") (pin "3") (pinfunction "D_3") (pintype "bidirectional"))
      (node (ref "Q4") (pin "3") (pinfunction "D_3") (pintype "bidirectional"))
      (node (ref "Q6") (pin "3") (pinfunction "D_3") (pintype "bidirectional"))
      (node (ref "Q9") (pin "3") (pinfunction "D_3") (pintype "bidirectional"))
      (node (ref "U$2") (pin "VOUT") (pinfunction "VOUT_VOUT") (pintype "bidirectional"))
    )
    (net (code "47") (name "GND") (class "Default")
      (node (ref "C1") (pin "2") (pinfunction "2_2") (pintype "passive"))
      (node (ref "C10") (pin "1") (pinfunction "1_1") (pintype "passive"))
      (node (ref "C11") (pin "2") (pinfunction "2_2") (pintype "passive"))
      (node (ref "C12") (pin "2") (pinfunction "2_2") (pintype "passive"))
      (node (ref "C13") (pin "2") (pinfunction "2_2") (pintype "passive"))
      (node (ref "C14") (pin "2") (pinfunction "2_2") (pintype "passive"))
      (node (ref "C15") (pin "2") (pinfunction "2_2") (pintype "passive"))
      (node (ref "C17") (pin "2") (pinfunction "2_2") (pintype "passive"))
      (node (ref "C19") (pin "2") (pinfunction "2_2") (pintype "passive"))
      (node (ref "C2") (pin "2") (pinfunction "2_2") (pintype "passive"))
      (node (ref "C20") (pin "1") (pinfunction "1_1") (pintype "passive"))
      (node (ref "C21") (pin "2") (pinfunction "2_2") (pintype "passive"))
      (node (ref "C22") (pin "2") (pinfunction "2_2") (pintype "passive"))
      (node (ref "C23") (pin "2") (pinfunction "2_2") (pintype "passive"))
      (node (ref "C24") (pin "2") (pinfunction "2_2") (pintype "passive"))
      (node (ref "C25") (pin "2") (pinfunction "2_2") (pintype "passive"))
      (node (ref "C26") (pin "1") (pinfunction "1_1") (pintype "passive"))
      (node (ref "C27") (pin "2") (pinfunction "2_2") (pintype "passive"))
      (node (ref "C3") (pin "2") (pinfunction "2_2") (pintype "passive"))
      (node (ref "C4") (pin "2") (pinfunction "2_2") (pintype "passive"))
      (node (ref "C5") (pin "2") (pinfunction "2_2") (pintype "passive"))
      (node (ref "C6") (pin "2") (pinfunction "2_2") (pintype "passive"))
      (node (ref "C7") (pin "2") (pinfunction "2_2") (pintype "passive"))
      (node (ref "C8") (pin "2") (pinfunction "2_2") (pintype "passive"))
      (node (ref "C9") (pin "1") (pinfunction "1_1") (pintype "passive"))
      (node (ref "D1") (pin "A") (pinfunction "A_A") (pintype "passive"))
      (node (ref "D2") (pin "A") (pinfunction "A_A") (pintype "passive"))
      (node (ref "I2C") (pin "3") (pinfunction "3_3") (pintype "passive"))
      (node (ref "IC3") (pin "12") (pinfunction "VSSA_12") (pintype "bidirectional"))
      (node (ref "IC3") (pin "18") (pinfunction "VSS_1_18") (pintype "bidirectional"))
      (node (ref "IC3") (pin "28") (pinfunction "PB2_28") (pintype "bidirectional"))
      (node (ref "IC3") (pin "63") (pinfunction "VSS_2_63") (pintype "bidirectional"))
      (node (ref "J1") (pin "6") (pinfunction "VSS_6") (pintype "bidirectional"))
      (node (ref "J1") (pin "MP1") (pinfunction "MP1_MP1") (pintype "bidirectional"))
      (node (ref "J1") (pin "MP3") (pinfunction "MP3_MP3") (pintype "bidirectional"))
      (node (ref "J1") (pin "MP5") (pinfunction "MP5_MP5") (pintype "bidirectional"))
      (node (ref "J1") (pin "MP6") (pinfunction "MP6_MP6") (pintype "bidirectional"))
      (node (ref "J2") (pin "5") (pinfunction "5_5") (pintype "bidirectional"))
      (node (ref "JP2") (pin "4") (pinfunction "4_4") (pintype "passive"))
      (node (ref "JP4") (pin "3") (pinfunction "3_3") (pintype "passive"))
      (node (ref "JP4") (pin "4") (pinfunction "4_4") (pintype "passive"))
      (node (ref "LED1") (pin "C") (pinfunction "C_C") (pintype "passive"))
      (node (ref "LED2") (pin "C") (pinfunction "C_C") (pintype "passive"))
      (node (ref "LED3") (pin "C") (pinfunction "C_C") (pintype "passive"))
      (node (ref "LED5") (pin "C") (pinfunction "C_C") (pintype "passive"))
      (node (ref "LED7") (pin "C") (pinfunction "C_C") (pintype "passive"))
      (node (ref "MPU9250") (pin "2") (pinfunction "2_2") (pintype "passive"))
      (node (ref "Q10") (pin "3") (pinfunction "S_3") (pintype "passive"))
      (node (ref "Q11") (pin "1") (pinfunction "G_1") (pintype "bidirectional"))
      (node (ref "Q12") (pin "1") (pinfunction "G_1") (pintype "bidirectional"))
      (node (ref "Q3") (pin "1") (pinfunction "G_1") (pintype "bidirectional"))
      (node (ref "R15") (pin "2") (pinfunction "2_2") (pintype "passive"))
      (node (ref "R20") (pin "1") (pinfunction "1_1") (pintype "passive"))
      (node (ref "R22") (pin "1") (pinfunction "1_1") (pintype "passive"))
      (node (ref "R24") (pin "2") (pinfunction "2_2") (pintype "passive"))
      (node (ref "R25") (pin "2") (pinfunction "2_2") (pintype "passive"))
      (node (ref "R3") (pin "1") (pinfunction "1_1") (pintype "passive"))
      (node (ref "R30") (pin "2") (pinfunction "2_2") (pintype "passive"))
      (node (ref "R33") (pin "2") (pinfunction "2_2") (pintype "passive"))
      (node (ref "R34") (pin "2") (pinfunction "2_2") (pintype "passive"))
      (node (ref "R36") (pin "2") (pinfunction "2_2") (pintype "passive"))
      (node (ref "R38") (pin "2") (pinfunction "2_2") (pintype "passive"))
      (node (ref "R41") (pin "1") (pinfunction "1_1") (pintype "passive"))
      (node (ref "R5") (pin "2") (pinfunction "2_2") (pintype "passive"))
      (node (ref "R7") (pin "1") (pinfunction "1_1") (pintype "passive"))
      (node (ref "S1") (pin "1") (pinfunction "P_1") (pintype "passive"))
      (node (ref "S1") (pin "3") (pinfunction "P1_3") (pintype "passive"))
      (node (ref "U$1") (pin "P$2") (pinfunction "P$2_P$2") (pintype "bidirectional"))
      (node (ref "U$2") (pin "GND") (pinfunction "GND_GND") (pintype "bidirectional"))
      (node (ref "U$2") (pin "HYS") (pinfunction "HYS_HYS") (pintype "bidirectional"))
      (node (ref "U$3") (pin "1ON/OFF") (pinfunction "1ON/OFF_1ON/OFF") (pintype "bidirectional"))
      (node (ref "U$3") (pin "3GND1") (pinfunction "3GND1_3GND1") (pintype "bidirectional"))
      (node (ref "U$3") (pin "3TGND2") (pinfunction "3GND2_3TGND2") (pintype "bidirectional"))
      (node (ref "U$3") (pin "7GND") (pinfunction "7GND_7GND") (pintype "bidirectional"))
      (node (ref "U$4") (pin "P$1") (pinfunction "P$1_P$1") (pintype "bidirectional"))
      (node (ref "U$4") (pin "P$10") (pinfunction "P$10_P$10") (pintype "bidirectional"))
      (node (ref "U$4") (pin "P$12") (pinfunction "P$12_P$12") (pintype "bidirectional"))
      (node (ref "U$4") (pin "P$19") (pinfunction "P$19_P$19") (pintype "bidirectional"))
      (node (ref "U$4") (pin "P$2") (pinfunction "P$2_P$2") (pintype "bidirectional"))
      (node (ref "U$4") (pin "P$20") (pinfunction "P$20_P$20") (pintype "bidirectional"))
      (node (ref "U$4") (pin "P$7") (pinfunction "P$7_P$7") (pintype "bidirectional"))
      (node (ref "U$5") (pin "GND") (pinfunction "GND_GND") (pintype "bidirectional"))
      (node (ref "U$6") (pin "P$2") (pinfunction "P$2_P$2") (pintype "bidirectional"))
      (node (ref "U$8") (pin "P$2") (pinfunction "P$2_P$2") (pintype "bidirectional"))
      (node (ref "U$9") (pin "P$5") (pinfunction "P$5_P$5") (pintype "bidirectional"))
      (node (ref "U$9") (pin "P$6") (pinfunction "P$6_P$6") (pintype "bidirectional"))
    )
    (net (code "48") (name "Net-(C10-Pad2)") (class "Default")
      (node (ref "C10") (pin "2") (pinfunction "2_2") (pintype "passive"))
      (node (ref "Q2") (pin "1") (pinfunction "1_1") (pintype "passive"))
      (node (ref "R1") (pin "1") (pinfunction "1_1") (pintype "passive"))
    )
    (net (code "49") (name "Net-(IC3-PB15)") (class "Default")
      (node (ref "IC3") (pin "36") (pinfunction "PB15_36") (pintype "bidirectional"))
      (node (ref "R6") (pin "2") (pinfunction "2_2") (pintype "passive"))
    )
    (net (code "50") (name "Net-(IC3-PC6)") (class "Default")
      (node (ref "C15") (pin "1") (pinfunction "1_1") (pintype "passive"))
      (node (ref "IC3") (pin "37") (pinfunction "PC6_37") (pintype "bidirectional"))
      (node (ref "R41") (pin "2") (pinfunction "2_2") (pintype "passive"))
      (node (ref "U$10") (pin "P$2") (pinfunction "P$2_P$2") (pintype "bidirectional"))
    )
    (net (code "51") (name "Net-(IC3-VCAP_1)") (class "Default")
      (node (ref "C19") (pin "1") (pinfunction "1_1") (pintype "passive"))
      (node (ref "IC3") (pin "31") (pinfunction "VCAP_1_31") (pintype "bidirectional"))
    )
    (net (code "52") (name "Net-(IC3-VCAP_2)") (class "Default")
      (node (ref "C8") (pin "1") (pinfunction "1_1") (pintype "passive"))
      (node (ref "IC3") (pin "47") (pinfunction "VCAP_2_47") (pintype "bidirectional"))
    )
    (net (code "53") (name "Net-(LED1-PadA)") (class "Default")
      (node (ref "LED1") (pin "A") (pinfunction "A_A") (pintype "passive"))
      (node (ref "R2") (pin "1") (pinfunction "1_1") (pintype "passive"))
    )
    (net (code "54") (name "Net-(LED2-PadA)") (class "Default")
      (node (ref "LED2") (pin "A") (pinfunction "A_A") (pintype "passive"))
      (node (ref "R21") (pin "2") (pinfunction "2_2") (pintype "passive"))
    )
    (net (code "55") (name "Net-(LED3-PadA)") (class "Default")
      (node (ref "LED3") (pin "A") (pinfunction "A_A") (pintype "passive"))
      (node (ref "R6") (pin "1") (pinfunction "1_1") (pintype "passive"))
    )
    (net (code "56") (name "Net-(LED5-PadA)") (class "Default")
      (node (ref "LED5") (pin "A") (pinfunction "A_A") (pintype "passive"))
      (node (ref "R16") (pin "1") (pinfunction "1_1") (pintype "passive"))
    )
    (net (code "57") (name "Net-(LED7-PadA)") (class "Default")
      (node (ref "LED7") (pin "A") (pinfunction "A_A") (pintype "passive"))
      (node (ref "R26") (pin "1") (pinfunction "1_1") (pintype "passive"))
    )
    (net (code "58") (name "Net-(Q1-G)") (class "Default")
      (node (ref "Q1") (pin "1") (pinfunction "G_1") (pintype "bidirectional"))
      (node (ref "Q4") (pin "1") (pinfunction "G_1") (pintype "bidirectional"))
      (node (ref "U$2") (pin "G3") (pinfunction "G3_G3") (pintype "bidirectional"))
    )
    (net (code "59") (name "Net-(Q1-S)") (class "Default")
      (node (ref "C6") (pin "1") (pinfunction "1_1") (pintype "passive"))
      (node (ref "Q1") (pin "2") (pinfunction "S_2") (pintype "bidirectional"))
      (node (ref "Q4") (pin "2") (pinfunction "S_2") (pintype "bidirectional"))
      (node (ref "U$2") (pin "VS3") (pinfunction "VS3_VS3") (pintype "bidirectional"))
    )
    (net (code "60") (name "Net-(Q3-S)") (class "Default")
      (node (ref "Q3") (pin "2") (pinfunction "S_2") (pintype "bidirectional"))
      (node (ref "U$6") (pin "P$1") (pinfunction "P$1_P$1") (pintype "bidirectional"))
    )
    (net (code "61") (name "Net-(Q5-G)") (class "Default")
      (node (ref "Q5") (pin "1") (pinfunction "G_1") (pintype "bidirectional"))
      (node (ref "Q6") (pin "1") (pinfunction "G_1") (pintype "bidirectional"))
      (node (ref "U$2") (pin "G2") (pinfunction "G2_G2") (pintype "bidirectional"))
    )
    (net (code "62") (name "Net-(Q5-S)") (class "Default")
      (node (ref "C5") (pin "1") (pinfunction "1_1") (pintype "passive"))
      (node (ref "Q5") (pin "2") (pinfunction "S_2") (pintype "bidirectional"))
      (node (ref "Q6") (pin "2") (pinfunction "S_2") (pintype "bidirectional"))
      (node (ref "U$2") (pin "VS2") (pinfunction "VS2_VS2") (pintype "bidirectional"))
    )
    (net (code "63") (name "Net-(Q7-G)") (class "Default")
      (node (ref "Q7") (pin "1") (pinfunction "G_1") (pintype "bidirectional"))
      (node (ref "Q9") (pin "1") (pinfunction "G_1") (pintype "bidirectional"))
      (node (ref "U$2") (pin "G1") (pinfunction "G1_G1") (pintype "bidirectional"))
    )
    (net (code "64") (name "Net-(Q7-S)") (class "Default")
      (node (ref "C4") (pin "1") (pinfunction "1_1") (pintype "passive"))
      (node (ref "Q7") (pin "2") (pinfunction "S_2") (pintype "bidirectional"))
      (node (ref "Q9") (pin "2") (pinfunction "S_2") (pintype "bidirectional"))
      (node (ref "U$2") (pin "VS1") (pinfunction "VS1_VS1") (pintype "bidirectional"))
    )
    (net (code "65") (name "Net-(Q8-D)") (class "Default")
      (node (ref "Q8") (pin "3") (pinfunction "D_3") (pintype "bidirectional"))
      (node (ref "TRANSISTER2") (pin "P$1") (pinfunction "P$1_P$1") (pintype "bidirectional"))
    )
    (net (code "66") (name "Net-(Q10-D)") (class "Default")
      (node (ref "Q10") (pin "2") (pinfunction "D_2") (pintype "passive"))
      (node (ref "U$7") (pin "P$2") (pinfunction "P$2_P$2") (pintype "bidirectional"))
    )
    (net (code "67") (name "Net-(Q10-G)") (class "Default")
      (node (ref "Q10") (pin "1") (pinfunction "G_1") (pintype "passive"))
      (node (ref "R24") (pin "1") (pinfunction "1_1") (pintype "passive"))
      (node (ref "TRANSISTER2") (pin "P$4") (pinfunction "P$4_P$4") (pintype "bidirectional"))
    )
    (net (code "68") (name "Net-(Q11-S)") (class "Default")
      (node (ref "Q11") (pin "2") (pinfunction "S_2") (pintype "bidirectional"))
      (node (ref "U$1") (pin "P$1") (pinfunction "P$1_P$1") (pintype "bidirectional"))
    )
    (net (code "69") (name "Net-(Q12-S)") (class "Default")
      (node (ref "Q12") (pin "2") (pinfunction "S_2") (pintype "bidirectional"))
      (node (ref "R21") (pin "1") (pinfunction "1_1") (pintype "passive"))
      (node (ref "TRANSISTER2") (pin "P$3") (pinfunction "P$3_P$3") (pintype "bidirectional"))
      (node (ref "U$7") (pin "P$1") (pinfunction "P$1_P$1") (pintype "bidirectional"))
      (node (ref "U$8") (pin "P$1") (pinfunction "P$1_P$1") (pintype "bidirectional"))
    )
    (net (code "70") (name "Net-(Q15-S)") (class "Default")
      (node (ref "Q15") (pin "2") (pinfunction "S_2") (pintype "bidirectional"))
      (node (ref "Q16") (pin "2") (pinfunction "S_2") (pintype "bidirectional"))
    )
    (net (code "71") (name "Net-(Q17-S)") (class "Default")
      (node (ref "JP3") (pin "2") (pinfunction "2_2") (pintype "passive"))
      (node (ref "Q17") (pin "2") (pinfunction "S_2") (pintype "bidirectional"))
    )
    (net (code "72") (name "Net-(R15-Pad1)") (class "Default")
      (node (ref "R15") (pin "1") (pinfunction "1_1") (pintype "passive"))
      (node (ref "R17") (pin "2") (pinfunction "2_2") (pintype "passive"))
      (node (ref "U$2") (pin "OV3") (pinfunction "OV3_OV3") (pintype "bidirectional"))
    )
    (net (code "73") (name "Net-(R16-Pad2)") (class "Default")
      (node (ref "R16") (pin "2") (pinfunction "2_2") (pintype "passive"))
      (node (ref "U$5") (pin "STATUS") (pinfunction "STATUS_STATUS") (pintype "bidirectional"))
    )
    (net (code "74") (name "Net-(R17-Pad1)") (class "Default")
      (node (ref "R17") (pin "1") (pinfunction "1_1") (pintype "passive"))
      (node (ref "R23") (pin "2") (pinfunction "2_2") (pintype "passive"))
      (node (ref "U$2") (pin "UV3") (pinfunction "UV3_UV3") (pintype "bidirectional"))
    )
    (net (code "75") (name "Net-(R22-Pad2)") (class "Default")
      (node (ref "R22") (pin "2") (pinfunction "2_2") (pintype "passive"))
      (node (ref "TRANSISTER2") (pin "P$2") (pinfunction "P$2_P$2") (pintype "bidirectional"))
    )
    (net (code "76") (name "Net-(R25-Pad1)") (class "Default")
      (node (ref "R25") (pin "1") (pinfunction "1_1") (pintype "passive"))
      (node (ref "R27") (pin "2") (pinfunction "2_2") (pintype "passive"))
      (node (ref "U$2") (pin "OV2") (pinfunction "OV2_OV2") (pintype "bidirectional"))
    )
    (net (code "77") (name "Net-(R27-Pad1)") (class "Default")
      (node (ref "R27") (pin "1") (pinfunction "1_1") (pintype "passive"))
      (node (ref "R29") (pin "2") (pinfunction "2_2") (pintype "passive"))
      (node (ref "U$2") (pin "UV2") (pinfunction "UV2_UV2") (pintype "bidirectional"))
    )
    (net (code "78") (name "Net-(R28-Pad2)") (class "Default")
      (node (ref "R28") (pin "2") (pinfunction "2_2") (pintype "passive"))
      (node (ref "U$9") (pin "P$3") (pinfunction "P$3_P$3") (pintype "bidirectional"))
      (node (ref "U$9") (pin "P$4") (pinfunction "P$4_P$4") (pintype "bidirectional"))
    )
    (net (code "79") (name "Net-(R30-Pad1)") (class "Default")
      (node (ref "R30") (pin "1") (pinfunction "1_1") (pintype "passive"))
      (node (ref "R31") (pin "2") (pinfunction "2_2") (pintype "passive"))
      (node (ref "U$2") (pin "OV1") (pinfunction "OV1_OV1") (pintype "bidirectional"))
    )
    (net (code "80") (name "Net-(R31-Pad1)") (class "Default")
      (node (ref "R31") (pin "1") (pinfunction "1_1") (pintype "passive"))
      (node (ref "R32") (pin "2") (pinfunction "2_2") (pintype "passive"))
      (node (ref "U$2") (pin "UV1") (pinfunction "UV1_UV1") (pintype "bidirectional"))
    )
    (net (code "81") (name "Net-(R35-Pad1)") (class "Default")
      (node (ref "R35") (pin "1") (pinfunction "1_1") (pintype "passive"))
      (node (ref "U$3") (pin "6TRIM") (pinfunction "6TRIM_6TRIM") (pintype "bidirectional"))
    )
    (net (code "82") (name "Net-(R35-Pad2)") (class "Default")
      (node (ref "R35") (pin "2") (pinfunction "2_2") (pintype "passive"))
      (node (ref "R36") (pin "1") (pinfunction "1_1") (pintype "passive"))
    )
    (net (code "83") (name "VCC") (class "Default")
      (node (ref "D3") (pin "A") (pinfunction "A_A") (pintype "passive"))
      (node (ref "J2") (pin "1") (pinfunction "1_1") (pintype "bidirectional"))
      (node (ref "Q15") (pin "1") (pinfunction "G_1") (pintype "bidirectional"))
      (node (ref "Q16") (pin "1") (pinfunction "G_1") (pintype "bidirectional"))
      (node (ref "R33") (pin "1") (pinfunction "1_1") (pintype "passive"))
      (node (ref "R8") (pin "2") (pinfunction "2_2") (pintype "passive"))
    )
    (net (code "84") (name "VDD") (class "Default")
      (node (ref "C13") (pin "1") (pinfunction "1_1") (pintype "passive"))
      (node (ref "C14") (pin "1") (pinfunction "1_1") (pintype "passive"))
      (node (ref "C20") (pin "2") (pinfunction "2_2") (pintype "passive"))
      (node (ref "C21") (pin "1") (pinfunction "1_1") (pintype "passive"))
      (node (ref "C22") (pin "1") (pinfunction "1_1") (pintype "passive"))
      (node (ref "C23") (pin "1") (pinfunction "1_1") (pintype "passive"))
      (node (ref "C24") (pin "1") (pinfunction "1_1") (pintype "passive"))
      (node (ref "C25") (pin "1") (pinfunction "1_1") (pintype "passive"))
      (node (ref "C26") (pin "2") (pinfunction "2_2") (pintype "passive"))
      (node (ref "I2C") (pin "4") (pinfunction "4_4") (pintype "passive"))
      (node (ref "IC3") (pin "1") (pinfunction "VBAT_1") (pintype "bidirectional"))
      (node (ref "IC3") (pin "13") (pinfunction "VDDA_13") (pintype "bidirectional"))
      (node (ref "IC3") (pin "19") (pinfunction "VDD_1_19") (pintype "bidirectional"))
      (node (ref "IC3") (pin "32") (pinfunction "VDD_2_32") (pintype "bidirectional"))
      (node (ref "IC3") (pin "48") (pinfunction "VDD_3_48") (pintype "bidirectional"))
      (node (ref "IC3") (pin "64") (pinfunction "VDD_4_64") (pintype "bidirectional"))
      (node (ref "J1") (pin "4") (pinfunction "VDD_4") (pintype "bidirectional"))
      (node (ref "J1") (pin "MP2") (pinfunction "MP2_MP2") (pintype "bidirectional"))
      (node (ref "JP2") (pin "3") (pinfunction "3_3") (pintype "passive"))
      (node (ref "JP4") (pin "1") (pinfunction "1_1") (pintype "passive"))
      (node (ref "JP4") (pin "2") (pinfunction "2_2") (pintype "passive"))
      (node (ref "MPU9250") (pin "1") (pinfunction "1_1") (pintype "passive"))
      (node (ref "R10") (pin "1") (pinfunction "1_1") (pintype "passive"))
      (node (ref "R11") (pin "1") (pinfunction "1_1") (pintype "passive"))
      (node (ref "R12") (pin "1") (pinfunction "1_1") (pintype "passive"))
      (node (ref "R13") (pin "1") (pinfunction "1_1") (pintype "passive"))
      (node (ref "R14") (pin "1") (pinfunction "1_1") (pintype "passive"))
      (node (ref "R18") (pin "2") (pinfunction "2_2") (pintype "passive"))
      (node (ref "R19") (pin "2") (pinfunction "2_2") (pintype "passive"))
      (node (ref "R2") (pin "2") (pinfunction "2_2") (pintype "passive"))
      (node (ref "R37") (pin "1") (pinfunction "1_1") (pintype "passive"))
      (node (ref "R38") (pin "1") (pinfunction "1_1") (pintype "passive"))
      (node (ref "R39") (pin "1") (pinfunction "1_1") (pintype "passive"))
      (node (ref "R40") (pin "1") (pinfunction "1_1") (pintype "passive"))
      (node (ref "R9") (pin "1") (pinfunction "1_1") (pintype "passive"))
      (node (ref "U$10") (pin "P$1") (pinfunction "P$1_P$1") (pintype "bidirectional"))
      (node (ref "U$3") (pin "4VOUT") (pinfunction "4VOUT_4VOUT") (pintype "bidirectional"))
      (node (ref "U$3") (pin "5SENSE") (pinfunction "5SENSE_5SENSE") (pintype "bidirectional"))
      (node (ref "U$4") (pin "P$14") (pinfunction "P$14_P$14") (pintype "bidirectional"))
      (node (ref "U$4") (pin "P$16") (pinfunction "P$16_P$16") (pintype "bidirectional"))
      (node (ref "U$5") (pin "VCC") (pinfunction "VCC_VCC") (pintype "bidirectional"))
      (node (ref "U$9") (pin "P$1") (pinfunction "P$1_P$1") (pintype "bidirectional"))
      (node (ref "U$9") (pin "P$2") (pinfunction "P$2_P$2") (pintype "bidirectional"))
    )
    (net (code "85") (name "unconnected-(IC3-PA8-Pad41)") (class "Default")
      (node (ref "IC3") (pin "41") (pinfunction "PA8_41") (pintype "bidirectional"))
    )
    (net (code "86") (name "unconnected-(IC3-PA9-Pad42)") (class "Default")
      (node (ref "IC3") (pin "42") (pinfunction "PA9_42") (pintype "bidirectional"))
    )
    (net (code "87") (name "unconnected-(IC3-PA10-Pad43)") (class "Default")
      (node (ref "IC3") (pin "43") (pinfunction "PA10_43") (pintype "bidirectional"))
    )
    (net (code "88") (name "unconnected-(IC3-PA15-Pad50)") (class "Default")
      (node (ref "IC3") (pin "50") (pinfunction "PA15_50") (pintype "bidirectional"))
    )
    (net (code "89") (name "unconnected-(IC3-PB8-Pad61)") (class "Default")
      (node (ref "IC3") (pin "61") (pinfunction "PB8_61") (pintype "bidirectional"))
    )
    (net (code "90") (name "unconnected-(IC3-PC0-Pad8)") (class "Default")
      (node (ref "IC3") (pin "8") (pinfunction "PC0_8") (pintype "bidirectional"))
    )
    (net (code "91") (name "unconnected-(IC3-PC1-Pad9)") (class "Default")
      (node (ref "IC3") (pin "9") (pinfunction "PC1_9") (pintype "bidirectional"))
    )
    (net (code "92") (name "unconnected-(IC3-PC2-Pad10)") (class "Default")
      (node (ref "IC3") (pin "10") (pinfunction "PC2_10") (pintype "bidirectional"))
    )
    (net (code "93") (name "unconnected-(IC3-PC3-Pad11)") (class "Default")
      (node (ref "IC3") (pin "11") (pinfunction "PC3_11") (pintype "bidirectional"))
    )
    (net (code "94") (name "unconnected-(IC3-PC7-Pad38)") (class "Default")
      (node (ref "IC3") (pin "38") (pinfunction "PC7_38") (pintype "bidirectional"))
    )
    (net (code "95") (name "unconnected-(IC3-PC13-Pad2)") (class "Default")
      (node (ref "IC3") (pin "2") (pinfunction "PC13_2") (pintype "bidirectional"))
    )
    (net (code "96") (name "unconnected-(IC3-PC14-Pad3)") (class "Default")
      (node (ref "IC3") (pin "3") (pinfunction "PC14_3") (pintype "bidirectional"))
    )
    (net (code "97") (name "unconnected-(IC3-PC15-Pad4)") (class "Default")
      (node (ref "IC3") (pin "4") (pinfunction "PC15_4") (pintype "bidirectional"))
    )
    (net (code "98") (name "unconnected-(J2-Pad4)") (class "Default")
      (node (ref "J2") (pin "4") (pinfunction "4_4") (pintype "bidirectional"))
    )
    (net (code "99") (name "unconnected-(JP4-Pad9)") (class "Default")
      (node (ref "JP4") (pin "9") (pinfunction "9_9") (pintype "passive"))
    )
    (net (code "100") (name "unconnected-(JP4-Pad11)") (class "Default")
      (node (ref "JP4") (pin "11") (pinfunction "11_11") (pintype "passive"))
    )
    (net (code "101") (name "unconnected-(MPU9250-Pad5)") (class "Default")
      (node (ref "MPU9250") (pin "5") (pinfunction "5_5") (pintype "passive"))
    )
    (net (code "102") (name "unconnected-(MPU9250-Pad6)") (class "Default")
      (node (ref "MPU9250") (pin "6") (pinfunction "6_6") (pintype "passive"))
    )
    (net (code "103") (name "unconnected-(MPU9250-Pad7)") (class "Default")
      (node (ref "MPU9250") (pin "7") (pinfunction "7_7") (pintype "passive"))
    )
    (net (code "104") (name "unconnected-(MPU9250-Pad8)") (class "Default")
      (node (ref "MPU9250") (pin "8") (pinfunction "8_8") (pintype "passive"))
    )
    (net (code "105") (name "unconnected-(MPU9250-Pad9)") (class "Default")
      (node (ref "MPU9250") (pin "9") (pinfunction "9_9") (pintype "passive"))
    )
    (net (code "106") (name "unconnected-(MPU9250-Pad10)") (class "Default")
      (node (ref "MPU9250") (pin "10") (pinfunction "10_10") (pintype "passive"))
    )
    (net (code "107") (name "unconnected-(U$2-PadCAS)") (class "Default")
      (node (ref "U$2") (pin "CAS") (pinfunction "CAS_CAS") (pintype "bidirectional"))
    )
    (net (code "108") (name "unconnected-(U$2-PadEN)") (class "Default")
      (node (ref "U$2") (pin "EN") (pinfunction "EN_EN") (pintype "bidirectional"))
    )
    (net (code "109") (name "unconnected-(U$2-PadSHDN)") (class "Default")
      (node (ref "U$2") (pin "SHDN") (pinfunction "SHDN_SHDN") (pintype "bidirectional"))
    )
    (net (code "110") (name "unconnected-(U$3-Pad9SEQUENCE)") (class "Default")
      (node (ref "U$3") (pin "9SEQUENCE") (pinfunction "9SEQUENCE_9SEQUENCE") (pintype "bidirectional"))
    )
    (net (code "111") (name "unconnected-(U$4-PadP$8)") (class "Default")
      (node (ref "U$4") (pin "P$8") (pinfunction "P$8_P$8") (pintype "bidirectional"))
    )
    (net (code "112") (name "unconnected-(U$4-PadP$9)") (class "Default")
      (node (ref "U$4") (pin "P$9") (pinfunction "P$9_P$9") (pintype "bidirectional"))
    )
    (net (code "113") (name "unconnected-(U$4-PadP$11)") (class "Default")
      (node (ref "U$4") (pin "P$11") (pinfunction "P$11_P$11") (pintype "bidirectional"))
    )
    (net (code "114") (name "unconnected-(U$4-PadP$13)") (class "Default")
      (node (ref "U$4") (pin "P$13") (pinfunction "P$13_P$13") (pintype "bidirectional"))
    )
    (net (code "115") (name "unconnected-(U$4-PadP$15)") (class "Default")
      (node (ref "U$4") (pin "P$15") (pinfunction "P$15_P$15") (pintype "bidirectional"))
    )
    (net (code "116") (name "unconnected-(U$4-PadP$17)") (class "Default")
      (node (ref "U$4") (pin "P$17") (pinfunction "P$17_P$17") (pintype "bidirectional"))
    )
    (net (code "117") (name "unconnected-(U$4-PadP$18)") (class "Default")
      (node (ref "U$4") (pin "P$18") (pinfunction "P$18_P$18") (pintype "bidirectional"))
    )
  )
)
